# design.net
KiCad netlist of a schematic drawn in Altium Designer
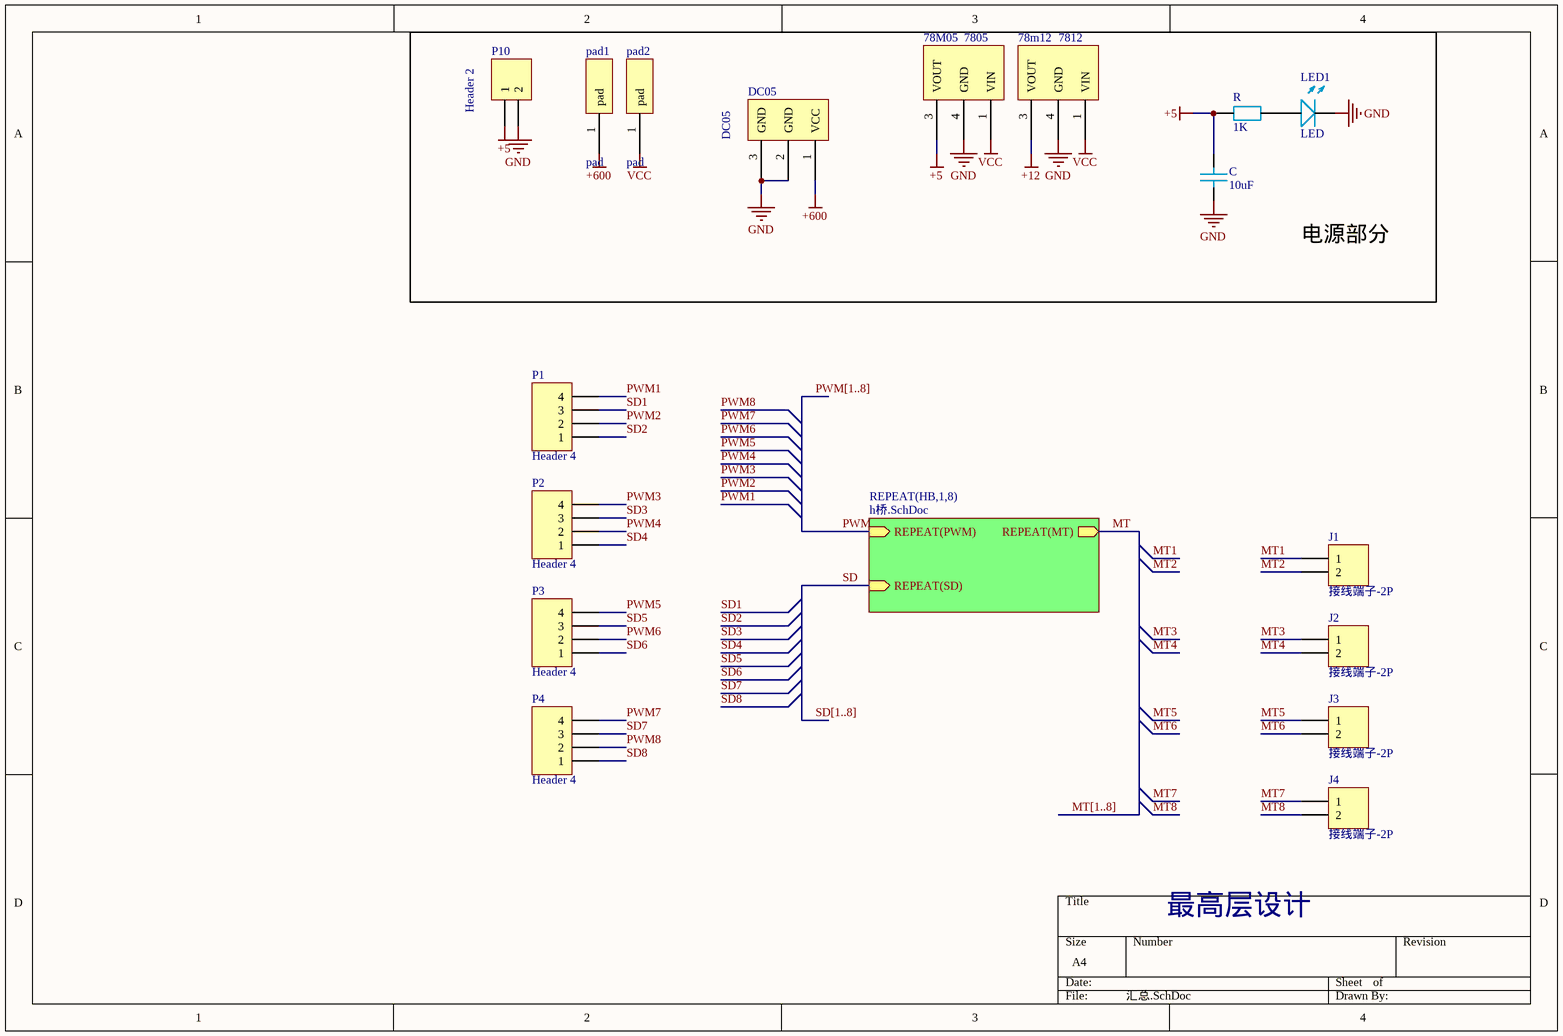
[diagram p0: 汇总.SchDoc]

(export (version "E")
  (design (tool "Eeschema 10.0.6"))
  (components
    (comp (ref "78M05") (value "7805") (footprint "78M05") (libsource (lib "elin私人订制") (part "7805")))
    (comp (ref "78m12") (value "7812") (footprint "78M05") (libsource (lib "elin私人订制") (part "7805")))
    (comp (ref "C") (value "10uF") (footprint "0805_C") (libsource (lib "elin私人订制") (part "C")))
    (comp (ref "DC05")
      (value "DC05")
      (footprint "DC-005 - duplicate")
      (description "DC05电源")
      (libsource (lib "elin私人订制") (part "DC05"))
    )
    (comp (ref "J1")
      (value "接线端子-2P")
      (footprint "KF128-5.08-2P")
      (description "通用接线端子")
      (libsource (lib "elin私人订制") (part "接线端子-2P"))
    )
    (comp (ref "J2")
      (value "接线端子-2P")
      (footprint "KF128-5.08-2P")
      (description "通用接线端子")
      (libsource (lib "elin私人订制") (part "接线端子-2P"))
    )
    (comp (ref "J3")
      (value "接线端子-2P")
      (footprint "KF128-5.08-2P")
      (description "通用接线端子")
      (libsource (lib "elin私人订制") (part "接线端子-2P"))
    )
    (comp (ref "J4")
      (value "接线端子-2P")
      (footprint "KF128-5.08-2P")
      (description "通用接线端子")
      (libsource (lib "elin私人订制") (part "接线端子-2P"))
    )
    (comp (ref "LED1") (value "LED") (footprint "LED_0805") (libsource (lib "elin私人订制") (part "LED")))
    (comp (ref "P1")
      (value "Header 4")
      (footprint "MX 1.25-WS-4P")
      (description "Header, 4-Pin")
      (fields (field (name "PUBLISHER") "Altium Limited"))
      (libsource (lib "elin私人订制") (part "Header 4"))
    )
    (comp (ref "P2")
      (value "Header 4")
      (footprint "MX 1.25-WS-4P")
      (description "Header, 4-Pin")
      (fields (field (name "PUBLISHER") "Altium Limited"))
      (libsource (lib "elin私人订制") (part "Header 4"))
    )
    (comp (ref "P3")
      (value "Header 4")
      (footprint "MX 1.25-WS-4P")
      (description "Header, 4-Pin")
      (fields (field (name "PUBLISHER") "Altium Limited"))
      (libsource (lib "elin私人订制") (part "Header 4"))
    )
    (comp (ref "P4")
      (value "Header 4")
      (footprint "MX 1.25-WS-4P")
      (description "Header, 4-Pin")
      (fields (field (name "PUBLISHER") "Altium Limited"))
      (libsource (lib "elin私人订制") (part "Header 4"))
    )
    (comp (ref "P10")
      (value "Header 2")
      (footprint "HDR1X2")
      (description "Header, 2-Pin")
      (fields (field (name "PUBLISHER") "Altium Limited"))
      (libsource (lib "elin私人订制") (part "Header 2"))
    )
    (comp (ref "pad1") (value "pad") (footprint "PAD3*3") (libsource (lib "elin私人订制") (part "pad1")))
    (comp (ref "pad2") (value "pad") (footprint "PAD3*3") (libsource (lib "elin私人订制") (part "pad1")))
    (comp (ref "R") (value "1K") (footprint "0805_R") (libsource (lib "elin私人订制") (part "R")))
  )
  (nets
    (net (code "1") (name "+5") (class "Default")
      (node (ref "78M05") (pin "3") (pinfunction "VOUT_3") (pintype "passive"))
      (node (ref "C") (pin "1") (pinfunction "1_1") (pintype "passive"))
      (node (ref "P10") (pin "1") (pinfunction "1_1") (pintype "passive"))
      (node (ref "R") (pin "1") (pinfunction "1_1") (pintype "passive"))
    )
    (net (code "2") (name "+12") (class "Default")
      (node (ref "78m12") (pin "3") (pinfunction "VOUT_3") (pintype "passive"))
    )
    (net (code "3") (name "+600") (class "Default")
      (node (ref "DC05") (pin "1") (pinfunction "VCC_1") (pintype "passive"))
      (node (ref "pad1") (pin "1") (pinfunction "pad_1") (pintype "passive"))
    )
    (net (code "5") (name "/MT1") (class "Default")
      (node (ref "J1") (pin "1") (pinfunction "1_1") (pintype "passive"))
    )
    (net (code "6") (name "/MT2") (class "Default")
      (node (ref "J1") (pin "2") (pinfunction "2_2") (pintype "passive"))
    )
    (net (code "7") (name "/MT3") (class "Default")
      (node (ref "J2") (pin "1") (pinfunction "1_1") (pintype "passive"))
    )
    (net (code "8") (name "/MT4") (class "Default")
      (node (ref "J2") (pin "2") (pinfunction "2_2") (pintype "passive"))
    )
    (net (code "9") (name "/MT5") (class "Default")
      (node (ref "J3") (pin "1") (pinfunction "1_1") (pintype "passive"))
    )
    (net (code "10") (name "/MT6") (class "Default")
      (node (ref "J3") (pin "2") (pinfunction "2_2") (pintype "passive"))
    )
    (net (code "11") (name "/MT7") (class "Default")
      (node (ref "J4") (pin "1") (pinfunction "1_1") (pintype "passive"))
    )
    (net (code "12") (name "/MT8") (class "Default")
      (node (ref "J4") (pin "2") (pinfunction "2_2") (pintype "passive"))
    )
    (net (code "15") (name "/PWM1") (class "Default")
      (node (ref "P1") (pin "4") (pinfunction "4_4") (pintype "passive"))
    )
    (net (code "16") (name "/PWM2") (class "Default")
      (node (ref "P1") (pin "2") (pinfunction "2_2") (pintype "passive"))
    )
    (net (code "17") (name "/PWM3") (class "Default")
      (node (ref "P2") (pin "4") (pinfunction "4_4") (pintype "passive"))
    )
    (net (code "18") (name "/PWM4") (class "Default")
      (node (ref "P2") (pin "2") (pinfunction "2_2") (pintype "passive"))
    )
    (net (code "19") (name "/PWM5") (class "Default")
      (node (ref "P3") (pin "4") (pinfunction "4_4") (pintype "passive"))
    )
    (net (code "20") (name "/PWM6") (class "Default")
      (node (ref "P3") (pin "2") (pinfunction "2_2") (pintype "passive"))
    )
    (net (code "21") (name "/PWM7") (class "Default")
      (node (ref "P4") (pin "4") (pinfunction "4_4") (pintype "passive"))
    )
    (net (code "22") (name "/PWM8") (class "Default")
      (node (ref "P4") (pin "2") (pinfunction "2_2") (pintype "passive"))
    )
    (net (code "25") (name "/SD1") (class "Default")
      (node (ref "P1") (pin "3") (pinfunction "3_3") (pintype "passive"))
    )
    (net (code "26") (name "/SD2") (class "Default")
      (node (ref "P1") (pin "1") (pinfunction "1_1") (pintype "passive"))
    )
    (net (code "27") (name "/SD3") (class "Default")
      (node (ref "P2") (pin "3") (pinfunction "3_3") (pintype "passive"))
    )
    (net (code "28") (name "/SD4") (class "Default")
      (node (ref "P2") (pin "1") (pinfunction "1_1") (pintype "passive"))
    )
    (net (code "29") (name "/SD5") (class "Default")
      (node (ref "P3") (pin "3") (pinfunction "3_3") (pintype "passive"))
    )
    (net (code "30") (name "/SD6") (class "Default")
      (node (ref "P3") (pin "1") (pinfunction "1_1") (pintype "passive"))
    )
    (net (code "31") (name "/SD7") (class "Default")
      (node (ref "P4") (pin "3") (pinfunction "3_3") (pintype "passive"))
    )
    (net (code "32") (name "/SD8") (class "Default")
      (node (ref "P4") (pin "1") (pinfunction "1_1") (pintype "passive"))
    )
    (net (code "34") (name "GND") (class "Default")
      (node (ref "78M05") (pin "4") (pinfunction "GND_4") (pintype "passive"))
      (node (ref "78m12") (pin "4") (pinfunction "GND_4") (pintype "passive"))
      (node (ref "C") (pin "2") (pinfunction "2_2") (pintype "passive"))
      (node (ref "DC05") (pin "2") (pinfunction "GND_2") (pintype "passive"))
      (node (ref "DC05") (pin "3") (pinfunction "GND_3") (pintype "passive"))
      (node (ref "LED1") (pin "2") (pinfunction "2_2") (pintype "passive"))
      (node (ref "P10") (pin "2") (pinfunction "2_2") (pintype "passive"))
    )
    (net (code "35") (name "Net-(LED1-Pad1)") (class "Default")
      (node (ref "LED1") (pin "1") (pinfunction "1_1") (pintype "passive"))
      (node (ref "R") (pin "2") (pinfunction "2_2") (pintype "passive"))
    )
    (net (code "36") (name "VCC") (class "Default")
      (node (ref "78M05") (pin "1") (pinfunction "VIN_1") (pintype "passive"))
      (node (ref "78m12") (pin "1") (pinfunction "VIN_1") (pintype "passive"))
      (node (ref "pad2") (pin "1") (pinfunction "pad_1") (pintype "passive"))
    )
  )
)
